# base.net
KiCad netlist of a schematic drawn in EAGLE
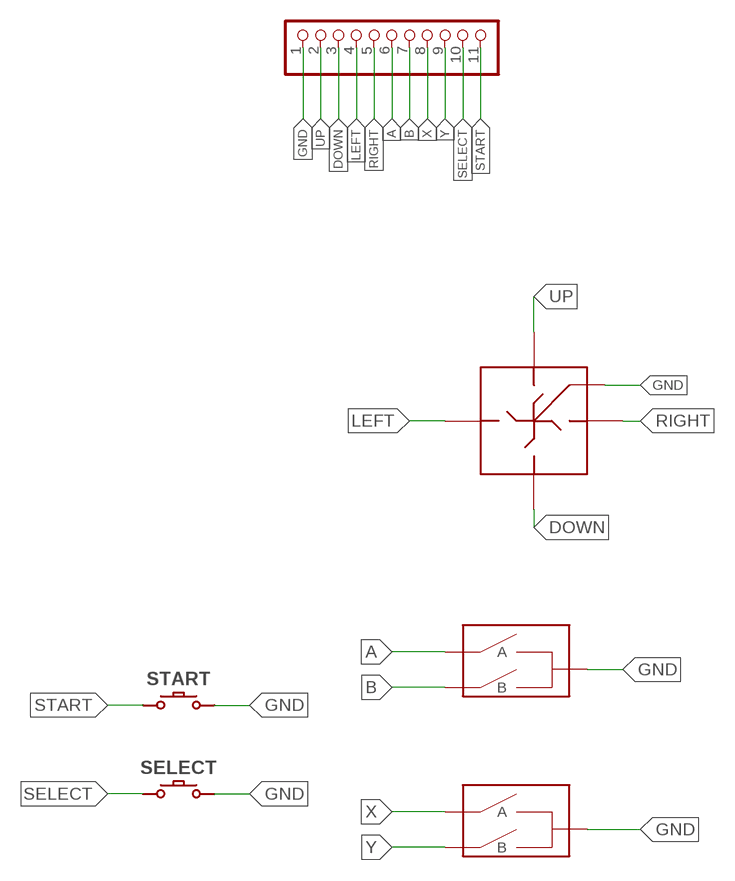
[diagram p0: schematic, sheet 1]

(export (version "E")
  (design (tool "Eeschema 10.0.6"))
  (components
    (comp (ref "GND")
      (value "PINHD-1X11_2.54")
      (footprint "eagle-import:1X11")
      (libsource (lib "eagle-import") (part "PINHD-1X11_2.54"))
    )
    (comp (ref "S1")
      (value "D-PAD")
      (footprint "eagle-import:D-PAD")
      (libsource (lib "eagle-import") (part "D-PAD"))
    )
    (comp (ref "S2")
      (value "XY_BUTTON")
      (footprint "eagle-import:AB_BUTTON")
      (libsource (lib "eagle-import") (part "AB_BUTTON"))
    )
    (comp (ref "S3")
      (value "AB_BUTTON")
      (footprint "eagle-import:AB_BUTTON")
      (libsource (lib "eagle-import") (part "AB_BUTTON"))
    )
    (comp (ref "SELECT")
      (value "CONDUCTIVE_BUTTON_STARTSELECTCONDUCTIVE_BUTTON_THICK_STARTSELECT")
      (footprint "eagle-import:CONDUCTIVE_BUTTON_THICK_STARTSELECT")
      (libsource (lib "eagle-import") (part "CONDUCTIVE_BUTTON_STARTSELECTCONDUCTIVE_BUTTON_THICK_STARTSELECT"))
    )
    (comp (ref "START")
      (value "CONDUCTIVE_BUTTON_STARTSELECTCONDUCTIVE_BUTTON_THICK_STARTSELECT")
      (footprint "eagle-import:CONDUCTIVE_BUTTON_THICK_STARTSELECT")
      (libsource (lib "eagle-import") (part "CONDUCTIVE_BUTTON_STARTSELECTCONDUCTIVE_BUTTON_THICK_STARTSELECT"))
    )
  )
  (nets
    (net (code "1") (name "A") (class "Default")
      (node (ref "GND") (pin "6") (pinfunction "6_6") (pintype "passive"))
      (node (ref "S3") (pin "A@1") (pinfunction "A_A@1") (pintype "bidirectional"))
      (node (ref "S3") (pin "A@2") (pinfunction "A_A@2") (pintype "bidirectional"))
    )
    (net (code "2") (name "B") (class "Default")
      (node (ref "GND") (pin "7") (pinfunction "7_7") (pintype "passive"))
      (node (ref "S3") (pin "B@1") (pinfunction "B_B@1") (pintype "bidirectional"))
      (node (ref "S3") (pin "B@2") (pinfunction "B_B@2") (pintype "bidirectional"))
    )
    (net (code "3") (name "DOWN") (class "Default")
      (node (ref "GND") (pin "3") (pinfunction "3_3") (pintype "passive"))
      (node (ref "S1") (pin "LEFT") (pinfunction "LEFT_LEFT") (pintype "bidirectional"))
    )
    (net (code "4") (name "GND") (class "Default")
      (node (ref "GND") (pin "1") (pinfunction "1_1") (pintype "passive"))
      (node (ref "S1") (pin "GND@1") (pinfunction "GND_GND@1") (pintype "bidirectional"))
      (node (ref "S1") (pin "GND@2") (pinfunction "GND_GND@2") (pintype "bidirectional"))
      (node (ref "S1") (pin "GND@3") (pinfunction "GND_GND@3") (pintype "bidirectional"))
      (node (ref "S1") (pin "GND@4") (pinfunction "GND_GND@4") (pintype "bidirectional"))
      (node (ref "S2") (pin "GND@1") (pinfunction "GND_GND@1") (pintype "bidirectional"))
      (node (ref "S2") (pin "GND@2") (pinfunction "GND_GND@2") (pintype "bidirectional"))
      (node (ref "S2") (pin "GND@3") (pinfunction "GND_GND@3") (pintype "bidirectional"))
      (node (ref "S2") (pin "GND@4") (pinfunction "GND_GND@4") (pintype "bidirectional"))
      (node (ref "S3") (pin "GND@1") (pinfunction "GND_GND@1") (pintype "bidirectional"))
      (node (ref "S3") (pin "GND@2") (pinfunction "GND_GND@2") (pintype "bidirectional"))
      (node (ref "S3") (pin "GND@3") (pinfunction "GND_GND@3") (pintype "bidirectional"))
      (node (ref "S3") (pin "GND@4") (pinfunction "GND_GND@4") (pintype "bidirectional"))
      (node (ref "SELECT") (pin "P$ACTIVE") (pinfunction "P$ACTIVE_P$ACTIVE") (pintype "bidirectional"))
      (node (ref "SELECT") (pin "P$ACTIVE1") (pinfunction "P$ACTIVE_P$ACTIVE1") (pintype "bidirectional"))
      (node (ref "SELECT") (pin "P$ACTIVE2") (pinfunction "P$ACTIVE_P$ACTIVE2") (pintype "bidirectional"))
      (node (ref "SELECT") (pin "P$ACTIVE3") (pinfunction "P$ACTIVE_P$ACTIVE3") (pintype "bidirectional"))
      (node (ref "START") (pin "P$ACTIVE") (pinfunction "P$ACTIVE_P$ACTIVE") (pintype "bidirectional"))
      (node (ref "START") (pin "P$ACTIVE1") (pinfunction "P$ACTIVE_P$ACTIVE1") (pintype "bidirectional"))
      (node (ref "START") (pin "P$ACTIVE2") (pinfunction "P$ACTIVE_P$ACTIVE2") (pintype "bidirectional"))
      (node (ref "START") (pin "P$ACTIVE3") (pinfunction "P$ACTIVE_P$ACTIVE3") (pintype "bidirectional"))
    )
    (net (code "5") (name "LEFT") (class "Default")
      (node (ref "GND") (pin "4") (pinfunction "4_4") (pintype "passive"))
      (node (ref "S1") (pin "UP") (pinfunction "UP_UP") (pintype "bidirectional"))
    )
    (net (code "6") (name "RIGHT") (class "Default")
      (node (ref "GND") (pin "5") (pinfunction "5_5") (pintype "passive"))
      (node (ref "S1") (pin "DOWN") (pinfunction "DOWN_DOWN") (pintype "bidirectional"))
    )
    (net (code "7") (name "SELECT") (class "Default")
      (node (ref "GND") (pin "10") (pinfunction "10_10") (pintype "passive"))
      (node (ref "SELECT") (pin "P$GND") (pinfunction "P$GND_P$GND") (pintype "bidirectional"))
      (node (ref "SELECT") (pin "P$GND1") (pinfunction "P$GND_P$GND1") (pintype "bidirectional"))
      (node (ref "SELECT") (pin "P$GND2") (pinfunction "P$GND_P$GND2") (pintype "bidirectional"))
      (node (ref "SELECT") (pin "P$GND3") (pinfunction "P$GND_P$GND3") (pintype "bidirectional"))
    )
    (net (code "8") (name "START") (class "Default")
      (node (ref "GND") (pin "11") (pinfunction "11_11") (pintype "passive"))
      (node (ref "START") (pin "P$GND") (pinfunction "P$GND_P$GND") (pintype "bidirectional"))
      (node (ref "START") (pin "P$GND1") (pinfunction "P$GND_P$GND1") (pintype "bidirectional"))
      (node (ref "START") (pin "P$GND2") (pinfunction "P$GND_P$GND2") (pintype "bidirectional"))
      (node (ref "START") (pin "P$GND3") (pinfunction "P$GND_P$GND3") (pintype "bidirectional"))
    )
    (net (code "9") (name "UP") (class "Default")
      (node (ref "GND") (pin "2") (pinfunction "2_2") (pintype "passive"))
      (node (ref "S1") (pin "RIGHT") (pinfunction "RIGHT_RIGHT") (pintype "bidirectional"))
    )
    (net (code "10") (name "X") (class "Default")
      (node (ref "GND") (pin "8") (pinfunction "8_8") (pintype "passive"))
      (node (ref "S2") (pin "A@1") (pinfunction "A_A@1") (pintype "bidirectional"))
      (node (ref "S2") (pin "A@2") (pinfunction "A_A@2") (pintype "bidirectional"))
    )
    (net (code "11") (name "Y") (class "Default")
      (node (ref "GND") (pin "9") (pinfunction "9_9") (pintype "passive"))
      (node (ref "S2") (pin "B@1") (pinfunction "B_B@1") (pintype "bidirectional"))
      (node (ref "S2") (pin "B@2") (pinfunction "B_B@2") (pintype "bidirectional"))
    )
  )
)
